# 2_ADSTM32-MCU.net
KiCad netlist of a schematic drawn in Altium Designer
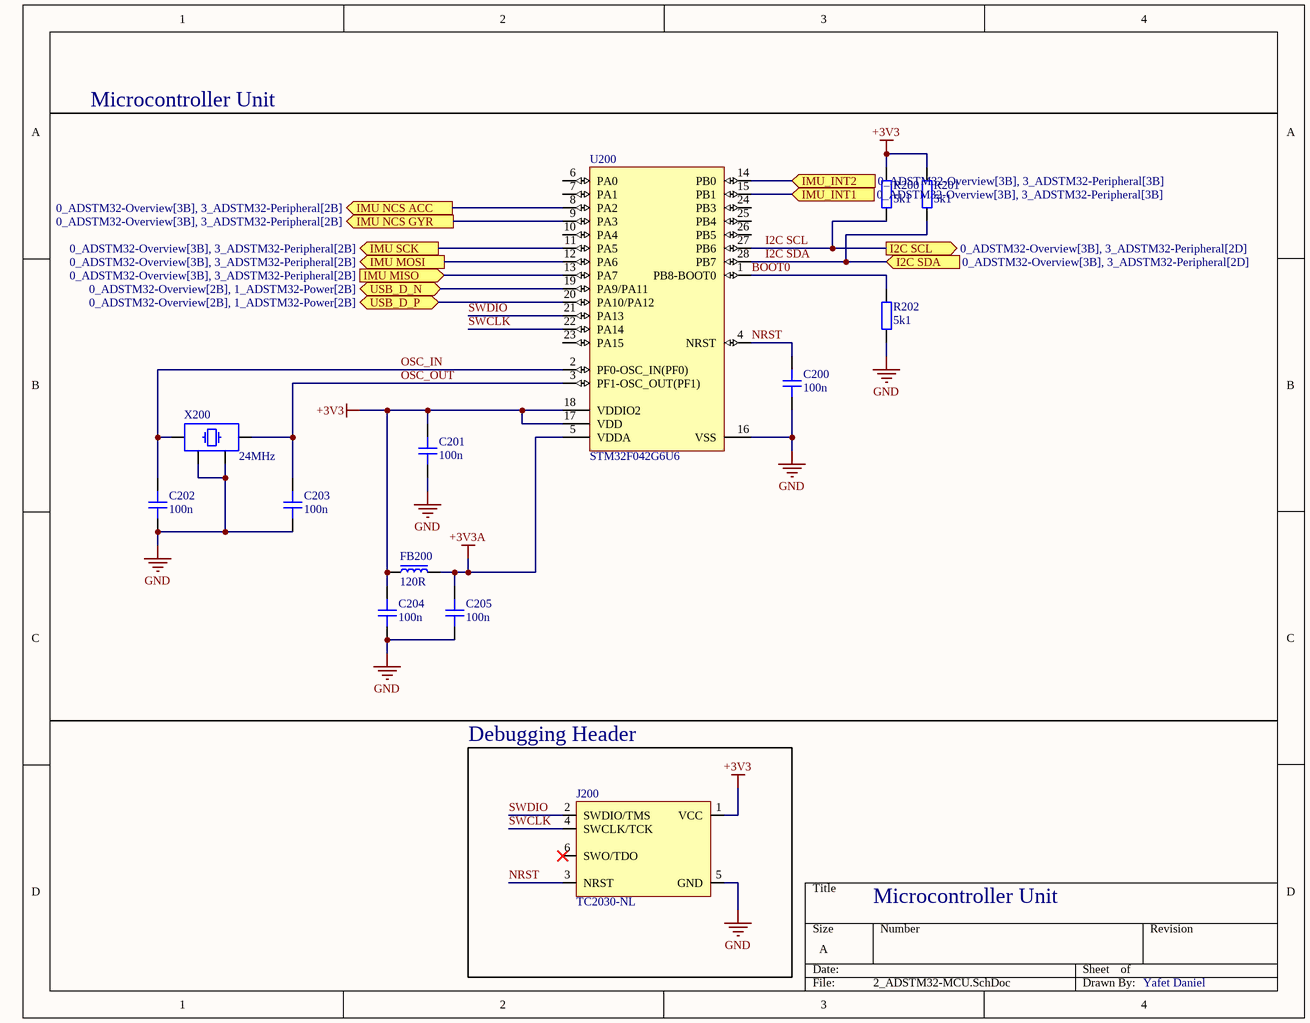
[diagram p0: 2_ADSTM32-MCU.SchDoc]

(export (version "E")
  (design (tool "Eeschema 10.0.6"))
  (components
    (comp (ref "C200")
      (value "100n")
      (footprint "CAP_0603")
      (description "Capacitor SMD 0603")
      (libsource (lib "Schematic-Lib-PhilsLab") (part "CAP_0603"))
    )
    (comp (ref "C201")
      (value "100n")
      (footprint "CAP_0603")
      (description "Capacitor SMD 0603")
      (libsource (lib "Schematic-Lib-PhilsLab") (part "CAP_0603"))
    )
    (comp (ref "C202")
      (value "100n")
      (footprint "CAP_0603")
      (description "Capacitor SMD 0603")
      (libsource (lib "Schematic-Lib-PhilsLab") (part "CAP_0603"))
    )
    (comp (ref "C203")
      (value "100n")
      (footprint "CAP_0603")
      (description "Capacitor SMD 0603")
      (libsource (lib "Schematic-Lib-PhilsLab") (part "CAP_0603"))
    )
    (comp (ref "C204")
      (value "100n")
      (footprint "CAP_0603")
      (description "Capacitor SMD 0603")
      (libsource (lib "Schematic-Lib-PhilsLab") (part "CAP_0603"))
    )
    (comp (ref "C205")
      (value "100n")
      (footprint "CAP_0603")
      (description "Capacitor SMD 0603")
      (libsource (lib "Schematic-Lib-PhilsLab") (part "CAP_0603"))
    )
    (comp (ref "FB200")
      (value "120R")
      (footprint "FB_0402")
      (description "Ferrite Bead SMD 0402")
      (libsource (lib "Schematic-Lib-PhilsLab") (part "FB_0402"))
    )
    (comp (ref "J200")
      (value "TC2030-NL")
      (footprint "TC2030-NL-FP")
      (description "Tag-Connect No-Solder SWD Debug Connector (No Legs) DO NOT PLACE")
      (fields
        (field (name "MANUFACTURER") "Tag-Connect")
        (field (name "MANUFACTURER PART NUMBER") "TC2030-NL-FP")
      )
      (libsource (lib "Schematic-Lib-PhilsLab") (part "TC2030-NL"))
    )
    (comp (ref "R200")
      (value "5k1")
      (footprint "RES_0603")
      (description "Resistor SMD 0603")
      (libsource (lib "Schematic-Lib-PhilsLab") (part "RES_0603"))
    )
    (comp (ref "R201")
      (value "5k1")
      (footprint "RES_0603")
      (description "Resistor SMD 0603")
      (libsource (lib "Schematic-Lib-PhilsLab") (part "RES_0603"))
    )
    (comp (ref "R202")
      (value "5k1")
      (footprint "RES_0603")
      (description "Resistor SMD 0603")
      (libsource (lib "Schematic-Lib-PhilsLab") (part "RES_0603"))
    )
    (comp (ref "U200")
      (value "STM32F042G6U6")
      (footprint "STM-UFQFPN28_V")
      (fields (field (name "MANUFACTURER") "STMicroelectronics"))
      (libsource (lib "Altium Content Vault") (part "MC-ARM-STM32F042-UFQFPN28"))
    )
    (comp (ref "X200")
      (value "24MHz")
      (footprint "XTAL_3225")
      (description "Crystal SMD 24MHz 10PPM 7pF 3225")
      (fields
        (field (name "MANUFACTURER") "Epson")
        (field (name "MANUFACTURER PART NUMBER") "TSX-3225 24.0000MF15X-AC")
      )
      (libsource (lib "Schematic-Lib-PhilsLab") (part "TSX-3225_24.0000MF15X-AC"))
    )
  )
  (nets
    (net (code "1") (name "+3V3") (class "Default")
      (node (ref "C201") (pin "2") (pinfunction "2_2") (pintype "passive"))
      (node (ref "C204") (pin "2") (pinfunction "2_2") (pintype "passive"))
      (node (ref "FB200") (pin "1") (pinfunction "1_1") (pintype "passive"))
      (node (ref "J200") (pin "1") (pinfunction "VCC_1") (pintype "passive"))
      (node (ref "R200") (pin "2") (pinfunction "2_2") (pintype "passive"))
      (node (ref "R201") (pin "2") (pinfunction "2_2") (pintype "passive"))
      (node (ref "U200") (pin "17") (pinfunction "VDD_17") (pintype "power_in"))
      (node (ref "U200") (pin "18") (pinfunction "VDDIO2_18") (pintype "power_in"))
    )
    (net (code "2") (name "+3V3A") (class "Default")
      (node (ref "C205") (pin "2") (pinfunction "2_2") (pintype "passive"))
      (node (ref "FB200") (pin "2") (pinfunction "2_2") (pintype "passive"))
      (node (ref "U200") (pin "5") (pinfunction "VDDA_5") (pintype "power_in"))
    )
    (net (code "3") (name "/BOOT0") (class "Default")
      (node (ref "R202") (pin "2") (pinfunction "2_2") (pintype "passive"))
      (node (ref "U200") (pin "1") (pinfunction "PB8-BOOT0_1") (pintype "bidirectional"))
    )
    (net (code "4") (name "/I2C SCL") (class "Default")
      (node (ref "R200") (pin "1") (pinfunction "1_1") (pintype "passive"))
      (node (ref "U200") (pin "27") (pinfunction "PB6_27") (pintype "bidirectional"))
    )
    (net (code "5") (name "/I2C SDA") (class "Default")
      (node (ref "R201") (pin "1") (pinfunction "1_1") (pintype "passive"))
      (node (ref "U200") (pin "28") (pinfunction "PB7_28") (pintype "bidirectional"))
    )
    (net (code "6") (name "/IMU MISO") (class "Default")
      (node (ref "U200") (pin "13") (pinfunction "PA7_13") (pintype "bidirectional"))
    )
    (net (code "7") (name "/IMU MOSI") (class "Default")
      (node (ref "U200") (pin "12") (pinfunction "PA6_12") (pintype "bidirectional"))
    )
    (net (code "8") (name "/IMU NCS ACC") (class "Default")
      (node (ref "U200") (pin "8") (pinfunction "PA2_8") (pintype "bidirectional"))
    )
    (net (code "9") (name "/IMU NCS GYR") (class "Default")
      (node (ref "U200") (pin "9") (pinfunction "PA3_9") (pintype "bidirectional"))
    )
    (net (code "10") (name "/IMU SCK") (class "Default")
      (node (ref "U200") (pin "11") (pinfunction "PA5_11") (pintype "bidirectional"))
    )
    (net (code "11") (name "/IMU_INT1") (class "Default")
      (node (ref "U200") (pin "15") (pinfunction "PB1_15") (pintype "bidirectional"))
    )
    (net (code "12") (name "/IMU_INT2") (class "Default")
      (node (ref "U200") (pin "14") (pinfunction "PB0_14") (pintype "bidirectional"))
    )
    (net (code "13") (name "/NRST") (class "Default")
      (node (ref "C200") (pin "2") (pinfunction "2_2") (pintype "passive"))
      (node (ref "J200") (pin "3") (pinfunction "NRST_3") (pintype "passive"))
      (node (ref "U200") (pin "4") (pinfunction "NRST_4") (pintype "bidirectional"))
    )
    (net (code "14") (name "/OSC_IN") (class "Default")
      (node (ref "C202") (pin "2") (pinfunction "2_2") (pintype "passive"))
      (node (ref "U200") (pin "2") (pinfunction "PF0-OSC_IN(PF0)_2") (pintype "bidirectional"))
      (node (ref "X200") (pin "1") (pinfunction "1_1") (pintype "passive"))
    )
    (net (code "15") (name "/OSC_OUT") (class "Default")
      (node (ref "C203") (pin "2") (pinfunction "2_2") (pintype "passive"))
      (node (ref "U200") (pin "3") (pinfunction "PF1-OSC_OUT(PF1)_3") (pintype "bidirectional"))
      (node (ref "X200") (pin "3") (pinfunction "3_3") (pintype "passive"))
    )
    (net (code "16") (name "/SWCLK") (class "Default")
      (node (ref "J200") (pin "4") (pinfunction "SWCLK/TCK_4") (pintype "passive"))
      (node (ref "U200") (pin "22") (pinfunction "PA14_22") (pintype "bidirectional"))
    )
    (net (code "17") (name "/SWDIO") (class "Default")
      (node (ref "J200") (pin "2") (pinfunction "SWDIO/TMS_2") (pintype "passive"))
      (node (ref "U200") (pin "21") (pinfunction "PA13_21") (pintype "bidirectional"))
    )
    (net (code "18") (name "/USB_D_N") (class "Default")
      (node (ref "U200") (pin "19") (pinfunction "PA9/PA11_19") (pintype "bidirectional"))
    )
    (net (code "19") (name "/USB_D_P") (class "Default")
      (node (ref "U200") (pin "20") (pinfunction "PA10/PA12_20") (pintype "bidirectional"))
    )
    (net (code "20") (name "GND") (class "Default")
      (node (ref "C200") (pin "1") (pinfunction "1_1") (pintype "passive"))
      (node (ref "C201") (pin "1") (pinfunction "1_1") (pintype "passive"))
      (node (ref "C202") (pin "1") (pinfunction "1_1") (pintype "passive"))
      (node (ref "C203") (pin "1") (pinfunction "1_1") (pintype "passive"))
      (node (ref "C204") (pin "1") (pinfunction "1_1") (pintype "passive"))
      (node (ref "C205") (pin "1") (pinfunction "1_1") (pintype "passive"))
      (node (ref "J200") (pin "5") (pinfunction "GND_5") (pintype "passive"))
      (node (ref "R202") (pin "1") (pinfunction "1_1") (pintype "passive"))
      (node (ref "U200") (pin "16") (pinfunction "VSS_16") (pintype "power_in"))
      (node (ref "X200") (pin "2") (pinfunction "2_2") (pintype "passive"))
      (node (ref "X200") (pin "4") (pinfunction "4_4") (pintype "passive"))
    )
    (net (code "21") (name "unconnected-(J200-SWO{slash}TDO-Pad6)") (class "Default")
      (node (ref "J200") (pin "6") (pinfunction "SWO/TDO_6") (pintype "passive+no_connect"))
    )
    (net (code "22") (name "unconnected-(U200-PA0-Pad6)") (class "Default")
      (node (ref "U200") (pin "6") (pinfunction "PA0_6") (pintype "bidirectional"))
    )
    (net (code "23") (name "unconnected-(U200-PA1-Pad7)") (class "Default")
      (node (ref "U200") (pin "7") (pinfunction "PA1_7") (pintype "bidirectional"))
    )
    (net (code "24") (name "unconnected-(U200-PA4-Pad10)") (class "Default")
      (node (ref "U200") (pin "10") (pinfunction "PA4_10") (pintype "bidirectional"))
    )
    (net (code "25") (name "unconnected-(U200-PA15-Pad23)") (class "Default")
      (node (ref "U200") (pin "23") (pinfunction "PA15_23") (pintype "bidirectional"))
    )
    (net (code "26") (name "unconnected-(U200-PB3-Pad24)") (class "Default")
      (node (ref "U200") (pin "24") (pinfunction "PB3_24") (pintype "bidirectional"))
    )
    (net (code "27") (name "unconnected-(U200-PB4-Pad25)") (class "Default")
      (node (ref "U200") (pin "25") (pinfunction "PB4_25") (pintype "bidirectional"))
    )
    (net (code "28") (name "unconnected-(U200-PB5-Pad26)") (class "Default")
      (node (ref "U200") (pin "26") (pinfunction "PB5_26") (pintype "bidirectional"))
    )
  )
)
